# MDAS_Controller_V1.net
KiCad netlist of a schematic drawn in EAGLE
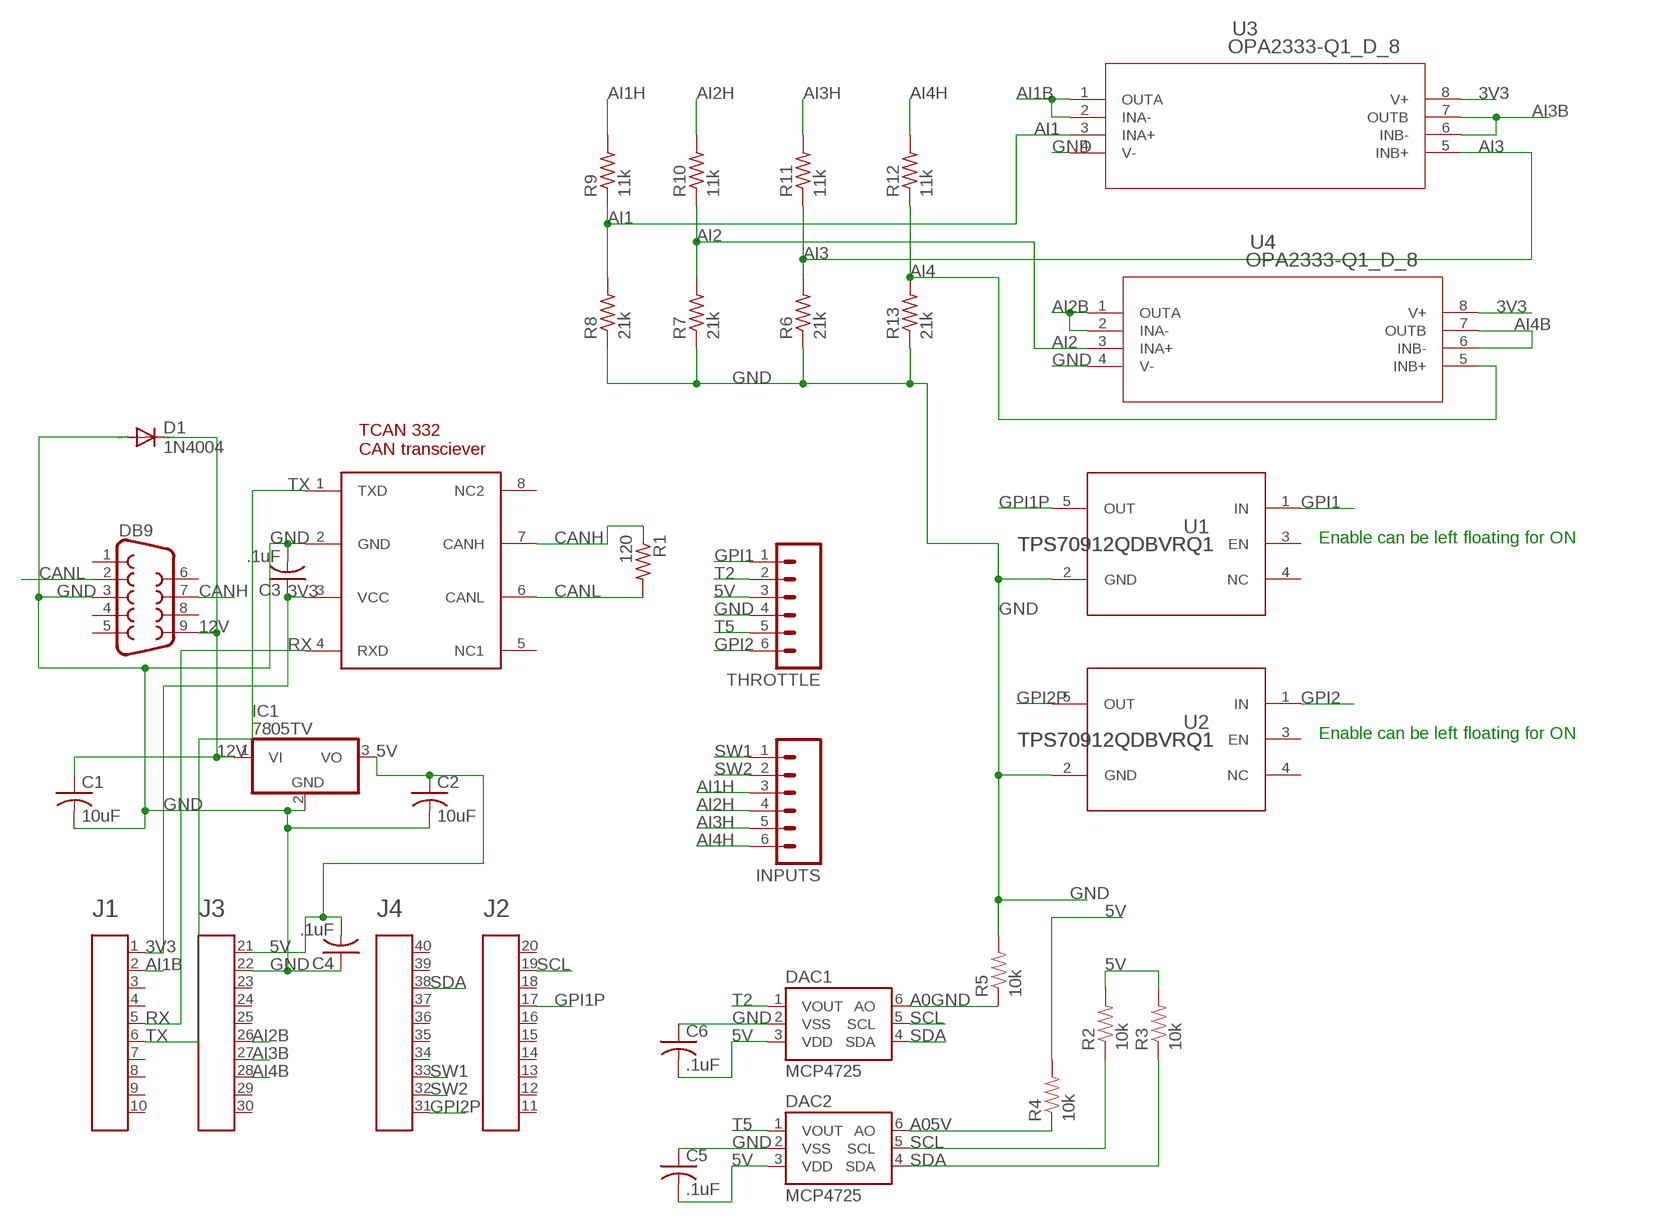
[diagram p0: schematic, sheet 1]

(export (version "E")
  (design (tool "Eeschema 10.0.6"))
  (components
    (comp (ref "A1")
      (value "HEADER4X10-BOOSTERPACK")
      (footprint "eagle-import:4X10-BOOSTERPACK")
      (libsource (lib "eagle-import") (part "HEADER4X10-BOOSTERPACK"))
    )
    (comp (ref "C1")
      (value "10uF")
      (footprint "eagle-import:C1206K")
      (libsource (lib "eagle-import") (part "C-USC1206K"))
    )
    (comp (ref "C2")
      (value "10uF")
      (footprint "eagle-import:C1206K")
      (libsource (lib "eagle-import") (part "C-USC1206K"))
    )
    (comp (ref "C3")
      (value ".1uF")
      (footprint "eagle-import:C0603")
      (libsource (lib "eagle-import") (part "adafruit_420_C-USC0603"))
    )
    (comp (ref "C4")
      (value ".1uF")
      (footprint "eagle-import:C0603")
      (libsource (lib "eagle-import") (part "adafruit_420_C-USC0603"))
    )
    (comp (ref "C5")
      (value ".1uF")
      (footprint "eagle-import:C0603")
      (libsource (lib "eagle-import") (part "adafruit_420_C-USC0603"))
    )
    (comp (ref "C6")
      (value ".1uF")
      (footprint "eagle-import:C0603")
      (libsource (lib "eagle-import") (part "adafruit_420_C-USC0603"))
    )
    (comp (ref "CAN_TRANSCIEVER")
      (value "TCAN332")
      (footprint "eagle-import:SOIC127P600X172-8N")
      (libsource (lib "eagle-import") (part "TCAN332"))
    )
    (comp (ref "D1")
      (value "1N4004")
      (footprint "eagle-import:DO41-10")
      (libsource (lib "eagle-import") (part "1N4004"))
    )
    (comp (ref "DAC1")
      (value "MCP4725")
      (footprint "eagle-import:SOT23-6")
      (libsource (lib "eagle-import") (part "MCP4725SOT-23"))
    )
    (comp (ref "DAC2")
      (value "MCP4725")
      (footprint "eagle-import:SOT23-6")
      (libsource (lib "eagle-import") (part "MCP4725SOT-23"))
    )
    (comp (ref "DB9")
      (value "DB9FEMALE")
      (footprint "eagle-import:DB9")
      (libsource (lib "eagle-import") (part "DB9FEMALE"))
    )
    (comp (ref "IC1")
      (value "7805TV")
      (footprint "eagle-import:TO220V")
      (libsource (lib "eagle-import") (part "78TV05"))
    )
    (comp (ref "INPUTS")
      (value "M06SMD-1MM")
      (footprint "eagle-import:1X06-1MM")
      (libsource (lib "eagle-import") (part "M06SMD-1MM"))
    )
    (comp (ref "R1")
      (value "120")
      (footprint "eagle-import:0207_10")
      (libsource (lib "eagle-import") (part "adafruit_420_R-US_0207/10"))
    )
    (comp (ref "R2")
      (value "10k")
      (footprint "eagle-import:0603-RES")
      (libsource (lib "eagle-import") (part "RESISTOR0603-RES"))
    )
    (comp (ref "R3")
      (value "10k")
      (footprint "eagle-import:0603-RES")
      (libsource (lib "eagle-import") (part "RESISTOR0603-RES"))
    )
    (comp (ref "R4")
      (value "10k")
      (footprint "eagle-import:0603-RES")
      (libsource (lib "eagle-import") (part "RESISTOR0603-RES"))
    )
    (comp (ref "R5")
      (value "10k")
      (footprint "eagle-import:0603-RES")
      (libsource (lib "eagle-import") (part "RESISTOR0603-RES"))
    )
    (comp (ref "R6")
      (value "21k")
      (footprint "eagle-import:R0603")
      (libsource (lib "eagle-import") (part "R-US_R0603"))
    )
    (comp (ref "R7")
      (value "21k")
      (footprint "eagle-import:R0603")
      (libsource (lib "eagle-import") (part "R-US_R0603"))
    )
    (comp (ref "R8")
      (value "21k")
      (footprint "eagle-import:R0603")
      (libsource (lib "eagle-import") (part "R-US_R0603"))
    )
    (comp (ref "R9")
      (value "11k")
      (footprint "eagle-import:R0603")
      (libsource (lib "eagle-import") (part "R-US_R0603"))
    )
    (comp (ref "R10")
      (value "11k")
      (footprint "eagle-import:R0603")
      (libsource (lib "eagle-import") (part "R-US_R0603"))
    )
    (comp (ref "R11")
      (value "11k")
      (footprint "eagle-import:R0603")
      (libsource (lib "eagle-import") (part "R-US_R0603"))
    )
    (comp (ref "R12")
      (value "11k")
      (footprint "eagle-import:R0603")
      (libsource (lib "eagle-import") (part "R-US_R0603"))
    )
    (comp (ref "R13")
      (value "21k")
      (footprint "eagle-import:R0603")
      (libsource (lib "eagle-import") (part "R-US_R0603"))
    )
    (comp (ref "THROTTLE")
      (value "M06SMD-1MM")
      (footprint "eagle-import:1X06-1MM")
      (libsource (lib "eagle-import") (part "M06SMD-1MM"))
    )
    (comp (ref "U1")
      (value "TPS70912QDBVRQ1")
      (footprint "eagle-import:DBV0005A_N")
      (libsource (lib "eagle-import") (part "TPS70912QDBVRQ1"))
    )
    (comp (ref "U2")
      (value "TPS70912QDBVRQ1")
      (footprint "eagle-import:DBV0005A_N")
      (libsource (lib "eagle-import") (part "TPS70912QDBVRQ1"))
    )
    (comp (ref "U3")
      (value "OPA2333-Q1_D_8")
      (footprint "eagle-import:D8")
      (fields (field (name "MANUFACTURER_PART_NUMBER") "opa2333q1_d_8"))
      (libsource (lib "eagle-import") (part "OPA2333-Q1_D_8"))
    )
    (comp (ref "U4")
      (value "OPA2333-Q1_D_8")
      (footprint "eagle-import:D8")
      (fields (field (name "MANUFACTURER_PART_NUMBER") "opa2333q1_d_8"))
      (libsource (lib "eagle-import") (part "OPA2333-Q1_D_8"))
    )
  )
  (nets
    (net (code "1") (name "/3V3") (class "Default")
      (node (ref "A1") (pin "1") (pinfunction "P$1_1") (pintype "bidirectional"))
      (node (ref "C3") (pin "1") (pinfunction "1_1") (pintype "passive"))
      (node (ref "CAN_TRANSCIEVER") (pin "3") (pinfunction "VCC_3") (pintype "bidirectional"))
      (node (ref "U3") (pin "8") (pinfunction "V+_8") (pintype "power_in"))
      (node (ref "U4") (pin "8") (pinfunction "V+_8") (pintype "power_in"))
    )
    (net (code "2") (name "/5V") (class "Default")
      (node (ref "A1") (pin "21") (pinfunction "P$21_21") (pintype "bidirectional"))
      (node (ref "C2") (pin "1") (pinfunction "1_1") (pintype "passive"))
      (node (ref "C4") (pin "2") (pinfunction "2_2") (pintype "passive"))
      (node (ref "C5") (pin "2") (pinfunction "2_2") (pintype "passive"))
      (node (ref "C6") (pin "2") (pinfunction "2_2") (pintype "passive"))
      (node (ref "DAC1") (pin "3") (pinfunction "VDD_3") (pintype "bidirectional"))
      (node (ref "DAC2") (pin "3") (pinfunction "VDD_3") (pintype "bidirectional"))
      (node (ref "IC1") (pin "3") (pinfunction "VO_3") (pintype "passive"))
      (node (ref "R2") (pin "2") (pinfunction "2_2") (pintype "passive"))
      (node (ref "R3") (pin "2") (pinfunction "2_2") (pintype "passive"))
      (node (ref "R4") (pin "2") (pinfunction "2_2") (pintype "passive"))
      (node (ref "THROTTLE") (pin "3") (pinfunction "3_3") (pintype "passive"))
    )
    (net (code "3") (name "/12V") (class "Default")
      (node (ref "C1") (pin "1") (pinfunction "1_1") (pintype "passive"))
      (node (ref "D1") (pin "C") (pinfunction "C_C") (pintype "passive"))
      (node (ref "DB9") (pin "9") (pinfunction "9_9") (pintype "passive"))
      (node (ref "IC1") (pin "1") (pinfunction "VI_1") (pintype "input"))
    )
    (net (code "4") (name "/A0GND") (class "Default")
      (node (ref "DAC1") (pin "6") (pinfunction "AO_6") (pintype "bidirectional"))
      (node (ref "R5") (pin "1") (pinfunction "1_1") (pintype "passive"))
    )
    (net (code "5") (name "/A05V") (class "Default")
      (node (ref "DAC2") (pin "6") (pinfunction "AO_6") (pintype "bidirectional"))
      (node (ref "R4") (pin "1") (pinfunction "1_1") (pintype "passive"))
    )
    (net (code "6") (name "/AI1") (class "Default")
      (node (ref "R8") (pin "2") (pinfunction "2_2") (pintype "passive"))
      (node (ref "R9") (pin "1") (pinfunction "1_1") (pintype "passive"))
      (node (ref "U3") (pin "3") (pinfunction "INA+_3") (pintype "input"))
    )
    (net (code "7") (name "/AI1B") (class "Default")
      (node (ref "A1") (pin "2") (pinfunction "P$2_2") (pintype "bidirectional"))
      (node (ref "U3") (pin "1") (pinfunction "OUTA_1") (pintype "output"))
      (node (ref "U3") (pin "2") (pinfunction "INA-_2") (pintype "input"))
    )
    (net (code "8") (name "/AI1H") (class "Default")
      (node (ref "INPUTS") (pin "3") (pinfunction "3_3") (pintype "passive"))
      (node (ref "R9") (pin "2") (pinfunction "2_2") (pintype "passive"))
    )
    (net (code "9") (name "/AI2") (class "Default")
      (node (ref "R10") (pin "1") (pinfunction "1_1") (pintype "passive"))
      (node (ref "R7") (pin "2") (pinfunction "2_2") (pintype "passive"))
      (node (ref "U4") (pin "3") (pinfunction "INA+_3") (pintype "input"))
    )
    (net (code "10") (name "/AI2B") (class "Default")
      (node (ref "A1") (pin "26") (pinfunction "P$26_26") (pintype "bidirectional"))
      (node (ref "U4") (pin "1") (pinfunction "OUTA_1") (pintype "output"))
      (node (ref "U4") (pin "2") (pinfunction "INA-_2") (pintype "input"))
    )
    (net (code "11") (name "/AI2H") (class "Default")
      (node (ref "INPUTS") (pin "4") (pinfunction "4_4") (pintype "passive"))
      (node (ref "R10") (pin "2") (pinfunction "2_2") (pintype "passive"))
    )
    (net (code "12") (name "/AI3") (class "Default")
      (node (ref "R11") (pin "1") (pinfunction "1_1") (pintype "passive"))
      (node (ref "R6") (pin "2") (pinfunction "2_2") (pintype "passive"))
      (node (ref "U3") (pin "5") (pinfunction "INB+_5") (pintype "input"))
    )
    (net (code "13") (name "/AI3B") (class "Default")
      (node (ref "A1") (pin "27") (pinfunction "P$27_27") (pintype "bidirectional"))
      (node (ref "U3") (pin "6") (pinfunction "INB-_6") (pintype "input"))
      (node (ref "U3") (pin "7") (pinfunction "OUTB_7") (pintype "output"))
    )
    (net (code "14") (name "/AI3H") (class "Default")
      (node (ref "INPUTS") (pin "5") (pinfunction "5_5") (pintype "passive"))
      (node (ref "R11") (pin "2") (pinfunction "2_2") (pintype "passive"))
    )
    (net (code "15") (name "/AI4") (class "Default")
      (node (ref "R12") (pin "1") (pinfunction "1_1") (pintype "passive"))
      (node (ref "R13") (pin "2") (pinfunction "2_2") (pintype "passive"))
      (node (ref "U4") (pin "5") (pinfunction "INB+_5") (pintype "input"))
    )
    (net (code "16") (name "/AI4B") (class "Default")
      (node (ref "A1") (pin "28") (pinfunction "P$28_28") (pintype "bidirectional"))
      (node (ref "U4") (pin "6") (pinfunction "INB-_6") (pintype "input"))
      (node (ref "U4") (pin "7") (pinfunction "OUTB_7") (pintype "output"))
    )
    (net (code "17") (name "/AI4H") (class "Default")
      (node (ref "INPUTS") (pin "6") (pinfunction "6_6") (pintype "passive"))
      (node (ref "R12") (pin "2") (pinfunction "2_2") (pintype "passive"))
    )
    (net (code "18") (name "/CANH") (class "Default")
      (node (ref "CAN_TRANSCIEVER") (pin "7") (pinfunction "CANH_7") (pintype "bidirectional"))
      (node (ref "DB9") (pin "7") (pinfunction "7_7") (pintype "passive"))
      (node (ref "R1") (pin "1") (pinfunction "1_1") (pintype "passive"))
    )
    (net (code "19") (name "/CANL") (class "Default")
      (node (ref "CAN_TRANSCIEVER") (pin "6") (pinfunction "CANL_6") (pintype "bidirectional"))
      (node (ref "DB9") (pin "2") (pinfunction "2_2") (pintype "passive"))
      (node (ref "R1") (pin "2") (pinfunction "2_2") (pintype "passive"))
    )
    (net (code "20") (name "/GND") (class "Default")
      (node (ref "A1") (pin "22") (pinfunction "P$22_22") (pintype "bidirectional"))
      (node (ref "C1") (pin "2") (pinfunction "2_2") (pintype "passive"))
      (node (ref "C2") (pin "2") (pinfunction "2_2") (pintype "passive"))
      (node (ref "C3") (pin "2") (pinfunction "2_2") (pintype "passive"))
      (node (ref "C4") (pin "1") (pinfunction "1_1") (pintype "passive"))
      (node (ref "C5") (pin "1") (pinfunction "1_1") (pintype "passive"))
      (node (ref "C6") (pin "1") (pinfunction "1_1") (pintype "passive"))
      (node (ref "CAN_TRANSCIEVER") (pin "2") (pinfunction "GND_2") (pintype "bidirectional"))
      (node (ref "D1") (pin "A") (pinfunction "A_A") (pintype "passive"))
      (node (ref "DAC1") (pin "2") (pinfunction "VSS_2") (pintype "bidirectional"))
      (node (ref "DAC2") (pin "2") (pinfunction "VSS_2") (pintype "bidirectional"))
      (node (ref "DB9") (pin "3") (pinfunction "3_3") (pintype "passive"))
      (node (ref "IC1") (pin "2") (pinfunction "GND_2") (pintype "passive"))
      (node (ref "R13") (pin "1") (pinfunction "1_1") (pintype "passive"))
      (node (ref "R5") (pin "2") (pinfunction "2_2") (pintype "passive"))
      (node (ref "R6") (pin "1") (pinfunction "1_1") (pintype "passive"))
      (node (ref "R7") (pin "1") (pinfunction "1_1") (pintype "passive"))
      (node (ref "R8") (pin "1") (pinfunction "1_1") (pintype "passive"))
      (node (ref "THROTTLE") (pin "4") (pinfunction "4_4") (pintype "passive"))
      (node (ref "U1") (pin "2") (pinfunction "GND_2") (pintype "power_in"))
      (node (ref "U2") (pin "2") (pinfunction "GND_2") (pintype "power_in"))
      (node (ref "U3") (pin "4") (pinfunction "V-_4") (pintype "power_in"))
      (node (ref "U4") (pin "4") (pinfunction "V-_4") (pintype "power_in"))
    )
    (net (code "21") (name "/GPI1") (class "Default")
      (node (ref "THROTTLE") (pin "1") (pinfunction "1_1") (pintype "passive"))
      (node (ref "U1") (pin "1") (pinfunction "IN_1") (pintype "power_in"))
    )
    (net (code "22") (name "/GPI1P") (class "Default")
      (node (ref "A1") (pin "17") (pinfunction "P$17_17") (pintype "bidirectional"))
      (node (ref "U1") (pin "5") (pinfunction "OUT_5") (pintype "power_in"))
    )
    (net (code "23") (name "/GPI2") (class "Default")
      (node (ref "THROTTLE") (pin "6") (pinfunction "6_6") (pintype "passive"))
      (node (ref "U2") (pin "1") (pinfunction "IN_1") (pintype "power_in"))
    )
    (net (code "24") (name "/GPI2P") (class "Default")
      (node (ref "A1") (pin "31") (pinfunction "P$31_31") (pintype "bidirectional"))
      (node (ref "U2") (pin "5") (pinfunction "OUT_5") (pintype "power_in"))
    )
    (net (code "25") (name "/RX") (class "Default")
      (node (ref "A1") (pin "5") (pinfunction "P$5_5") (pintype "bidirectional"))
      (node (ref "CAN_TRANSCIEVER") (pin "4") (pinfunction "RXD_4") (pintype "bidirectional"))
    )
    (net (code "26") (name "/SCL") (class "Default")
      (node (ref "A1") (pin "19") (pinfunction "P$19_19") (pintype "bidirectional"))
      (node (ref "DAC1") (pin "5") (pinfunction "SCL_5") (pintype "bidirectional"))
      (node (ref "DAC2") (pin "5") (pinfunction "SCL_5") (pintype "bidirectional"))
      (node (ref "R2") (pin "1") (pinfunction "1_1") (pintype "passive"))
    )
    (net (code "27") (name "/SDA") (class "Default")
      (node (ref "A1") (pin "38") (pinfunction "P$38_38") (pintype "bidirectional"))
      (node (ref "DAC1") (pin "4") (pinfunction "SDA_4") (pintype "bidirectional"))
      (node (ref "DAC2") (pin "4") (pinfunction "SDA_4") (pintype "bidirectional"))
      (node (ref "R3") (pin "1") (pinfunction "1_1") (pintype "passive"))
    )
    (net (code "28") (name "/SW1") (class "Default")
      (node (ref "A1") (pin "33") (pinfunction "P$33_33") (pintype "bidirectional"))
      (node (ref "INPUTS") (pin "1") (pinfunction "1_1") (pintype "passive"))
    )
    (net (code "29") (name "/SW2") (class "Default")
      (node (ref "A1") (pin "32") (pinfunction "P$32_32") (pintype "bidirectional"))
      (node (ref "INPUTS") (pin "2") (pinfunction "2_2") (pintype "passive"))
    )
    (net (code "30") (name "/T2") (class "Default")
      (node (ref "DAC1") (pin "1") (pinfunction "VOUT_1") (pintype "bidirectional"))
      (node (ref "THROTTLE") (pin "2") (pinfunction "2_2") (pintype "passive"))
    )
    (net (code "31") (name "/T5") (class "Default")
      (node (ref "DAC2") (pin "1") (pinfunction "VOUT_1") (pintype "bidirectional"))
      (node (ref "THROTTLE") (pin "5") (pinfunction "5_5") (pintype "passive"))
    )
    (net (code "32") (name "/TX") (class "Default")
      (node (ref "A1") (pin "6") (pinfunction "P$6_6") (pintype "bidirectional"))
      (node (ref "CAN_TRANSCIEVER") (pin "1") (pinfunction "TXD_1") (pintype "bidirectional"))
    )
    (net (code "33") (name "unconnected-(A1-P$3-Pad3)") (class "Default")
      (node (ref "A1") (pin "3") (pinfunction "P$3_3") (pintype "bidirectional"))
    )
    (net (code "34") (name "unconnected-(A1-P$4-Pad4)") (class "Default")
      (node (ref "A1") (pin "4") (pinfunction "P$4_4") (pintype "bidirectional"))
    )
    (net (code "35") (name "unconnected-(A1-P$7-Pad7)") (class "Default")
      (node (ref "A1") (pin "7") (pinfunction "P$7_7") (pintype "bidirectional"))
    )
    (net (code "36") (name "unconnected-(A1-P$8-Pad8)") (class "Default")
      (node (ref "A1") (pin "8") (pinfunction "P$8_8") (pintype "bidirectional"))
    )
    (net (code "37") (name "unconnected-(A1-P$9-Pad9)") (class "Default")
      (node (ref "A1") (pin "9") (pinfunction "P$9_9") (pintype "bidirectional"))
    )
    (net (code "38") (name "unconnected-(A1-P$10-Pad10)") (class "Default")
      (node (ref "A1") (pin "10") (pinfunction "P$10_10") (pintype "bidirectional"))
    )
    (net (code "39") (name "unconnected-(A1-P$11-Pad11)") (class "Default")
      (node (ref "A1") (pin "11") (pinfunction "P$11_11") (pintype "bidirectional"))
    )
    (net (code "40") (name "unconnected-(A1-P$12-Pad12)") (class "Default")
      (node (ref "A1") (pin "12") (pinfunction "P$12_12") (pintype "bidirectional"))
    )
    (net (code "41") (name "unconnected-(A1-P$13-Pad13)") (class "Default")
      (node (ref "A1") (pin "13") (pinfunction "P$13_13") (pintype "bidirectional"))
    )
    (net (code "42") (name "unconnected-(A1-P$14-Pad14)") (class "Default")
      (node (ref "A1") (pin "14") (pinfunction "P$14_14") (pintype "bidirectional"))
    )
    (net (code "43") (name "unconnected-(A1-P$15-Pad15)") (class "Default")
      (node (ref "A1") (pin "15") (pinfunction "P$15_15") (pintype "bidirectional"))
    )
    (net (code "44") (name "unconnected-(A1-P$16-Pad16)") (class "Default")
      (node (ref "A1") (pin "16") (pinfunction "P$16_16") (pintype "bidirectional"))
    )
    (net (code "45") (name "unconnected-(A1-P$18-Pad18)") (class "Default")
      (node (ref "A1") (pin "18") (pinfunction "P$18_18") (pintype "bidirectional"))
    )
    (net (code "46") (name "unconnected-(A1-P$20-Pad20)") (class "Default")
      (node (ref "A1") (pin "20") (pinfunction "P$20_20") (pintype "bidirectional"))
    )
    (net (code "47") (name "unconnected-(A1-P$23-Pad23)") (class "Default")
      (node (ref "A1") (pin "23") (pinfunction "P$23_23") (pintype "bidirectional"))
    )
    (net (code "48") (name "unconnected-(A1-P$24-Pad24)") (class "Default")
      (node (ref "A1") (pin "24") (pinfunction "P$24_24") (pintype "bidirectional"))
    )
    (net (code "49") (name "unconnected-(A1-P$25-Pad25)") (class "Default")
      (node (ref "A1") (pin "25") (pinfunction "P$25_25") (pintype "bidirectional"))
    )
    (net (code "50") (name "unconnected-(A1-P$29-Pad29)") (class "Default")
      (node (ref "A1") (pin "29") (pinfunction "P$29_29") (pintype "bidirectional"))
    )
    (net (code "51") (name "unconnected-(A1-P$30-Pad30)") (class "Default")
      (node (ref "A1") (pin "30") (pinfunction "P$30_30") (pintype "bidirectional"))
    )
    (net (code "52") (name "unconnected-(A1-P$34-Pad34)") (class "Default")
      (node (ref "A1") (pin "34") (pinfunction "P$34_34") (pintype "bidirectional"))
    )
    (net (code "53") (name "unconnected-(A1-P$35-Pad35)") (class "Default")
      (node (ref "A1") (pin "35") (pinfunction "P$35_35") (pintype "bidirectional"))
    )
    (net (code "54") (name "unconnected-(A1-P$36-Pad36)") (class "Default")
      (node (ref "A1") (pin "36") (pinfunction "P$36_36") (pintype "bidirectional"))
    )
    (net (code "55") (name "unconnected-(A1-P$37-Pad37)") (class "Default")
      (node (ref "A1") (pin "37") (pinfunction "P$37_37") (pintype "bidirectional"))
    )
    (net (code "56") (name "unconnected-(A1-P$39-Pad39)") (class "Default")
      (node (ref "A1") (pin "39") (pinfunction "P$39_39") (pintype "bidirectional"))
    )
    (net (code "57") (name "unconnected-(A1-P$40-Pad40)") (class "Default")
      (node (ref "A1") (pin "40") (pinfunction "P$40_40") (pintype "bidirectional"))
    )
    (net (code "58") (name "unconnected-(CAN_TRANSCIEVER-NC1-Pad5)") (class "Default")
      (node (ref "CAN_TRANSCIEVER") (pin "5") (pinfunction "NC1_5") (pintype "bidirectional"))
    )
    (net (code "59") (name "unconnected-(CAN_TRANSCIEVER-NC2-Pad8)") (class "Default")
      (node (ref "CAN_TRANSCIEVER") (pin "8") (pinfunction "NC2_8") (pintype "bidirectional"))
    )
    (net (code "60") (name "unconnected-(DB9-Pad1)") (class "Default")
      (node (ref "DB9") (pin "1") (pinfunction "1_1") (pintype "passive"))
    )
    (net (code "61") (name "unconnected-(DB9-Pad4)") (class "Default")
      (node (ref "DB9") (pin "4") (pinfunction "4_4") (pintype "passive"))
    )
    (net (code "62") (name "unconnected-(DB9-Pad5)") (class "Default")
      (node (ref "DB9") (pin "5") (pinfunction "5_5") (pintype "passive"))
    )
    (net (code "63") (name "unconnected-(DB9-Pad6)") (class "Default")
      (node (ref "DB9") (pin "6") (pinfunction "6_6") (pintype "passive"))
    )
    (net (code "64") (name "unconnected-(DB9-Pad8)") (class "Default")
      (node (ref "DB9") (pin "8") (pinfunction "8_8") (pintype "passive"))
    )
    (net (code "65") (name "unconnected-(U1-EN-Pad3)") (class "Default")
      (node (ref "U1") (pin "3") (pinfunction "EN_3") (pintype "input"))
    )
    (net (code "66") (name "unconnected-(U1-NC-Pad4)") (class "Default")
      (node (ref "U1") (pin "4") (pinfunction "NC_4") (pintype "passive"))
    )
    (net (code "67") (name "unconnected-(U2-EN-Pad3)") (class "Default")
      (node (ref "U2") (pin "3") (pinfunction "EN_3") (pintype "input"))
    )
    (net (code "68") (name "unconnected-(U2-NC-Pad4)") (class "Default")
      (node (ref "U2") (pin "4") (pinfunction "NC_4") (pintype "passive"))
    )
  )
)
